# 03.net
KiCad netlist of a schematic drawn in Altium Designer
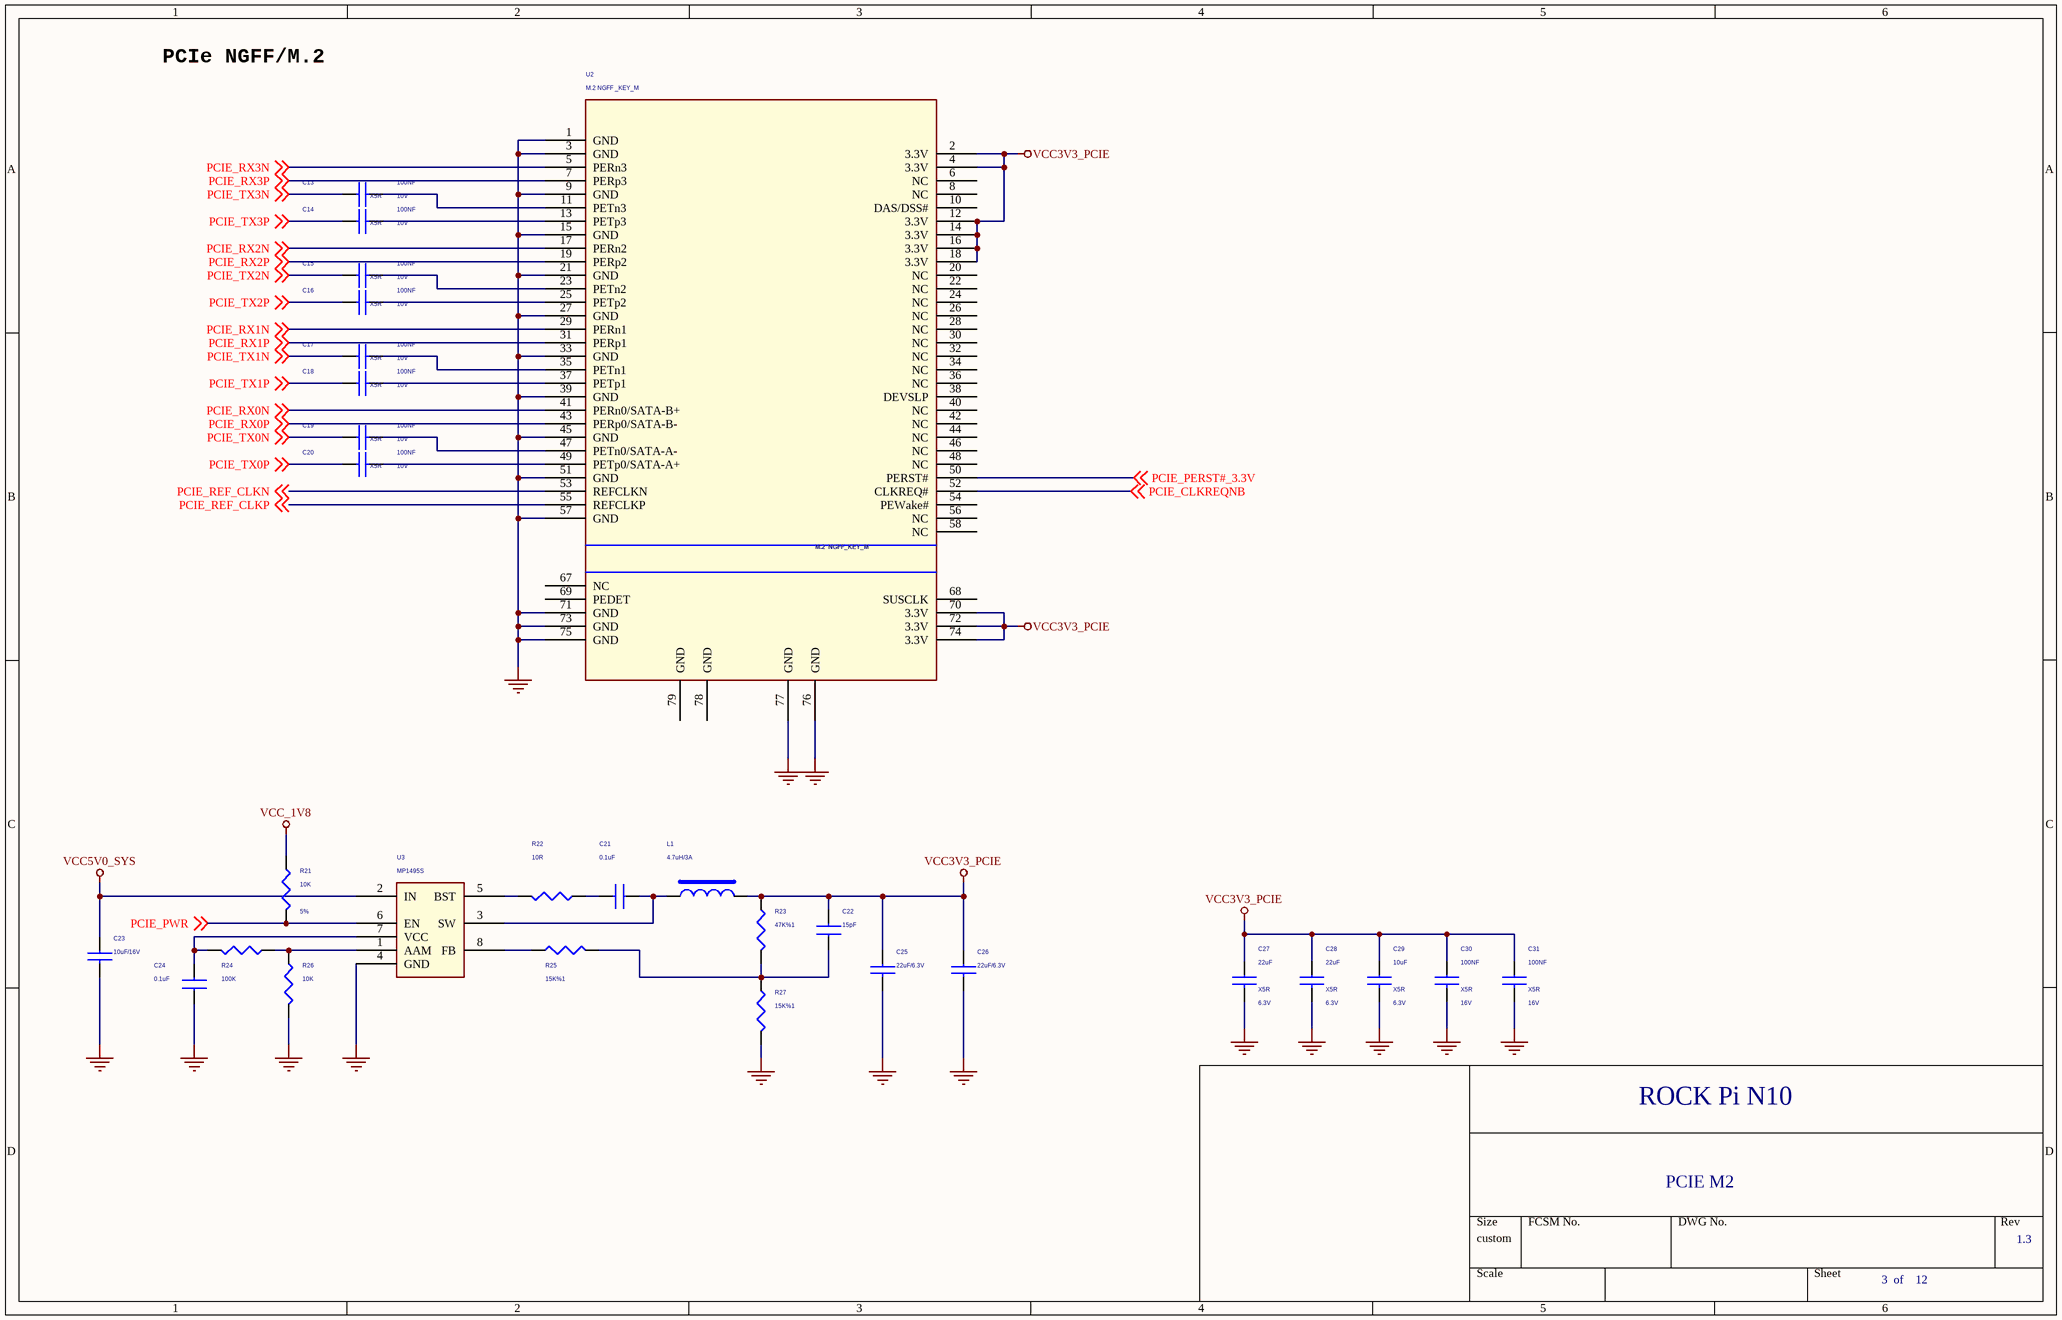
[diagram p0: 03.SchDoc]

(export (version "E")
  (design (tool "Eeschema 10.0.6"))
  (components
    (comp (ref "C13")
      (value "100NF")
      (footprint "C0201")
      (description "cap,100.00nF,+/-10%,10V,X5R,C0201")
      (fields
        (field (name "DIELECTRIC") "X5R")
        (field (name "VOLTAGE") "10V")
        (field (name "MANUFACTURER") "TDK")
        (field (name "TOLERANCE") "10%")
        (field (name "CREATED BY") "JJJ")
      )
      (libsource (lib "*") (part "CAP NP_2"))
    )
    (comp (ref "C14")
      (value "100NF")
      (footprint "C0201")
      (description "cap,100.00nF,+/-10%,10V,X5R,C0201")
      (fields
        (field (name "DIELECTRIC") "X5R")
        (field (name "VOLTAGE") "10V")
        (field (name "MANUFACTURER") "TDK")
        (field (name "TOLERANCE") "10%")
        (field (name "CREATED BY") "JJJ")
      )
      (libsource (lib "*") (part "CAP NP_2"))
    )
    (comp (ref "C15")
      (value "100NF")
      (footprint "C0201")
      (description "cap,100.00nF,+/-10%,10V,X5R,C0201")
      (fields
        (field (name "DIELECTRIC") "X5R")
        (field (name "VOLTAGE") "10V")
        (field (name "MANUFACTURER") "TDK")
        (field (name "TOLERANCE") "10%")
        (field (name "CREATED BY") "JJJ")
      )
      (libsource (lib "*") (part "CAP NP_2"))
    )
    (comp (ref "C16")
      (value "100NF")
      (footprint "C0201")
      (description "cap,100.00nF,+/-10%,10V,X5R,C0201")
      (fields
        (field (name "DIELECTRIC") "X5R")
        (field (name "VOLTAGE") "10V")
        (field (name "MANUFACTURER") "TDK")
        (field (name "TOLERANCE") "10%")
        (field (name "CREATED BY") "JJJ")
      )
      (libsource (lib "*") (part "CAP NP_2"))
    )
    (comp (ref "C17")
      (value "100NF")
      (footprint "C0201")
      (description "cap,100.00nF,+/-10%,10V,X5R,C0201")
      (fields
        (field (name "DIELECTRIC") "X5R")
        (field (name "VOLTAGE") "10V")
        (field (name "MANUFACTURER") "TDK")
        (field (name "TOLERANCE") "10%")
        (field (name "CREATED BY") "JJJ")
      )
      (libsource (lib "*") (part "CAP NP_2"))
    )
    (comp (ref "C18")
      (value "100NF")
      (footprint "C0201")
      (description "cap,100.00nF,+/-10%,10V,X5R,C0201")
      (fields
        (field (name "DIELECTRIC") "X5R")
        (field (name "VOLTAGE") "10V")
        (field (name "MANUFACTURER") "TDK")
        (field (name "TOLERANCE") "10%")
        (field (name "CREATED BY") "JJJ")
      )
      (libsource (lib "*") (part "CAP NP_2"))
    )
    (comp (ref "C19")
      (value "100NF")
      (footprint "C0201")
      (description "cap,100.00nF,+/-10%,10V,X5R,C0201")
      (fields
        (field (name "DIELECTRIC") "X5R")
        (field (name "VOLTAGE") "10V")
        (field (name "TOLERANCE") "10%")
        (field (name "MANUFACTURER") "TDK")
        (field (name "CREATED BY") "JJJ")
      )
      (libsource (lib "*") (part "CAP NP_2"))
    )
    (comp (ref "C20")
      (value "100NF")
      (footprint "C0201")
      (description "cap,100.00nF,+/-10%,10V,X5R,C0201")
      (fields
        (field (name "DIELECTRIC") "X5R")
        (field (name "VOLTAGE") "10V")
        (field (name "TOLERANCE") "10%")
        (field (name "MANUFACTURER") "TDK")
        (field (name "CREATED BY") "JJJ")
      )
      (libsource (lib "*") (part "CAP NP_2"))
    )
    (comp (ref "C21")
      (value "0.1uF")
      (footprint "C0603")
      (description "RoHS CHIP CAP 1uF +10/-10% 16V X5R")
      (libsource (lib "*") (part "CAP NP_Dup3"))
    )
    (comp (ref "C22")
      (value "15pF")
      (footprint "C0603")
      (description "RoHS CHIP CAP 1uF +10/-10% 16V X5R")
      (libsource (lib "*") (part "CAP NP_Dup3"))
    )
    (comp (ref "C23") (value "10uF/16V") (footprint "C0805") (libsource (lib "*") (part "CAP NP_2_Dup1")))
    (comp (ref "C24")
      (value "0.1uF")
      (footprint "C0603")
      (description "RoHS CHIP CAP 1uF +10/-10% 16V X5R")
      (libsource (lib "*") (part "CAP NP_Dup3"))
    )
    (comp (ref "C25") (value "22uF/6.3V") (footprint "C0805") (libsource (lib "*") (part "CAP NP_2_Dup1")))
    (comp (ref "C26") (value "22uF/6.3V") (footprint "C0805") (libsource (lib "*") (part "CAP NP_2_Dup1")))
    (comp (ref "C27")
      (value "22uF")
      (footprint "C0805")
      (description "cap,22.00uF,+/-20%,6.3V,X5R,C0603")
      (fields
        (field (name "DIELECTRIC") "X5R")
        (field (name "VOLTAGE") "6.3V")
        (field (name "MANUFACTURER") "TDK")
        (field (name "TOLERANCE") "20%")
        (field (name "CREATED BY") "JJJ")
      )
      (libsource (lib "*") (part "CAP NP_2"))
    )
    (comp (ref "C28")
      (value "22uF")
      (footprint "C0805")
      (description "cap,22.00uF,+/-20%,6.3V,X5R,C0603")
      (fields
        (field (name "DIELECTRIC") "X5R")
        (field (name "VOLTAGE") "6.3V")
        (field (name "MANUFACTURER") "TDK")
        (field (name "TOLERANCE") "20%")
        (field (name "CREATED BY") "JJJ")
      )
      (libsource (lib "*") (part "CAP NP_2"))
    )
    (comp (ref "C29")
      (value "10uF")
      (footprint "C0603")
      (description "cap,10.00uF,+/-10%,6.3V,X5R,C0603")
      (fields
        (field (name "DIELECTRIC") "X5R")
        (field (name "VOLTAGE") "6.3V")
        (field (name "MANUFACTURER") "TDK")
        (field (name "TOLERANCE") "10%")
        (field (name "CREATED BY") "JJJ")
      )
      (libsource (lib "*") (part "CAP NP_2"))
    )
    (comp (ref "C30")
      (value "100NF")
      (footprint "C0402")
      (description "cap,100.00nF,+/-10%,16V,X5R,C0402")
      (fields
        (field (name "DIELECTRIC") "X5R")
        (field (name "VOLTAGE") "16V")
        (field (name "TOLERANCE") "10%")
        (field (name "MANUFACTURER") "TDK")
        (field (name "CREATED BY") "JJJ")
      )
      (libsource (lib "*") (part "CAP NP_2"))
    )
    (comp (ref "C31")
      (value "100NF")
      (footprint "C0402")
      (description "cap,100.00nF,+/-10%,16V,X5R,C0402")
      (fields
        (field (name "DIELECTRIC") "X5R")
        (field (name "VOLTAGE") "16V")
        (field (name "MANUFACTURER") "TDK")
        (field (name "TOLERANCE") "10%")
        (field (name "CREATED BY") "JJJ")
      )
      (libsource (lib "*") (part "CAP NP_2"))
    )
    (comp (ref "L1")
      (value "4.7uH/3A")
      (footprint "IND-6X6")
      (libsource (lib "*") (part "INDUCTORS OF FERRITE_Dup1"))
    )
    (comp (ref "R21")
      (value "10K")
      (footprint "R0402")
      (description "通用厚膜电阻,10K,+/-5%,R0402,1/16W.")
      (fields
        (field (name "TOLERANCE") "5%")
        (field (name "MANUFACTURER") "YAGEO")
        (field (name "CREATED BY") "YTL")
      )
      (libsource (lib "*") (part "RESISTOR_3"))
    )
    (comp (ref "R22")
      (value "10R")
      (footprint "R0402")
      (description "RES,thick film,47KOhm,+/-5%,1/16W,SMD0402")
      (libsource (lib "*") (part "RESISTOR_0"))
    )
    (comp (ref "R23")
      (value "47K%1")
      (footprint "R0402")
      (description "RES,thick film,47KOhm,+/-5%,1/16W,SMD0402")
      (libsource (lib "*") (part "RESISTOR_0"))
    )
    (comp (ref "R24")
      (value "100K")
      (footprint "R0402")
      (description "RES,thick film,47KOhm,+/-5%,1/16W,SMD0402")
      (libsource (lib "*") (part "RESISTOR_0"))
    )
    (comp (ref "R25")
      (value "15K%1")
      (footprint "R0402")
      (description "RES,thick film,47KOhm,+/-5%,1/16W,SMD0402")
      (libsource (lib "*") (part "RESISTOR_0"))
    )
    (comp (ref "R26")
      (value "10K")
      (footprint "R0402")
      (description "RES,thick film,47KOhm,+/-5%,1/16W,SMD0402")
      (libsource (lib "*") (part "RESISTOR_0"))
    )
    (comp (ref "R27")
      (value "15K%1")
      (footprint "R0402")
      (description "RES,thick film,47KOhm,+/-5%,1/16W,SMD0402")
      (libsource (lib "*") (part "RESISTOR_0"))
    )
    (comp (ref "U2")
      (value "M.2 NGFF _KEY_M")
      (footprint "M2_NGFF_KEY_M")
      (libsource (lib "*") (part "M_5.2 NGFF EKEY SOCKET"))
    )
    (comp (ref "U3") (value "MP1495S") (footprint "TSOT_23_8") (libsource (lib "*") (part "BUCK-MP1495")))
  )
  (nets
    (net (code "1") (name "GND") (class "Default")
      (node (ref "C23") (pin "2") (pinfunction "2_2") (pintype "passive"))
      (node (ref "C24") (pin "1") (pinfunction "1_1") (pintype "passive"))
      (node (ref "C25") (pin "2") (pinfunction "2_2") (pintype "passive"))
      (node (ref "C26") (pin "2") (pinfunction "2_2") (pintype "passive"))
      (node (ref "C27") (pin "2") (pinfunction "2_2") (pintype "passive"))
      (node (ref "C28") (pin "2") (pinfunction "2_2") (pintype "passive"))
      (node (ref "C29") (pin "2") (pinfunction "2_2") (pintype "passive"))
      (node (ref "C30") (pin "2") (pinfunction "2_2") (pintype "passive"))
      (node (ref "C31") (pin "2") (pinfunction "2_2") (pintype "passive"))
      (node (ref "R26") (pin "2") (pinfunction "2_2") (pintype "passive"))
      (node (ref "R27") (pin "2") (pinfunction "2_2") (pintype "passive"))
      (node (ref "U2") (pin "1") (pinfunction "GND_1") (pintype "passive"))
      (node (ref "U2") (pin "15") (pinfunction "GND_15") (pintype "passive"))
      (node (ref "U2") (pin "21") (pinfunction "GND_21") (pintype "passive"))
      (node (ref "U2") (pin "27") (pinfunction "GND_27") (pintype "passive"))
      (node (ref "U2") (pin "3") (pinfunction "GND_3") (pintype "passive"))
      (node (ref "U2") (pin "33") (pinfunction "GND_33") (pintype "passive"))
      (node (ref "U2") (pin "39") (pinfunction "GND_39") (pintype "passive"))
      (node (ref "U2") (pin "45") (pinfunction "GND_45") (pintype "passive"))
      (node (ref "U2") (pin "51") (pinfunction "GND_51") (pintype "passive"))
      (node (ref "U2") (pin "57") (pinfunction "GND_57") (pintype "passive"))
      (node (ref "U2") (pin "71") (pinfunction "GND_71") (pintype "passive"))
      (node (ref "U2") (pin "73") (pinfunction "GND_73") (pintype "passive"))
      (node (ref "U2") (pin "75") (pinfunction "GND_75") (pintype "passive"))
      (node (ref "U2") (pin "76") (pinfunction "GND_76") (pintype "passive"))
      (node (ref "U2") (pin "77") (pinfunction "GND_77") (pintype "passive"))
      (node (ref "U2") (pin "9") (pinfunction "GND_9") (pintype "passive"))
      (node (ref "U3") (pin "4") (pinfunction "GND_4") (pintype "passive"))
    )
    (net (code "2") (name "Net-(C21-Pad2)") (class "Default")
      (node (ref "C21") (pin "2") (pinfunction "2_2") (pintype "passive"))
      (node (ref "R22") (pin "1") (pinfunction "1_1") (pintype "passive"))
    )
    (net (code "3") (name "Net-(C22-Pad1)") (class "Default")
      (node (ref "C22") (pin "1") (pinfunction "1_1") (pintype "passive"))
      (node (ref "R23") (pin "2") (pinfunction "2_2") (pintype "passive"))
      (node (ref "R25") (pin "2") (pinfunction "2_2") (pintype "passive"))
      (node (ref "R27") (pin "1") (pinfunction "1_1") (pintype "passive"))
    )
    (net (code "4") (name "Net-(U2-PETn0{slash}SATA-A-)") (class "Default")
      (node (ref "C19") (pin "2") (pinfunction "2_2") (pintype "passive"))
      (node (ref "U2") (pin "47") (pinfunction "PETn0/SATA-A-_47") (pintype "passive"))
    )
    (net (code "5") (name "Net-(U2-PETn1)") (class "Default")
      (node (ref "C17") (pin "2") (pinfunction "2_2") (pintype "passive"))
      (node (ref "U2") (pin "35") (pinfunction "PETn1_35") (pintype "passive"))
    )
    (net (code "6") (name "Net-(U2-PETn2)") (class "Default")
      (node (ref "C15") (pin "2") (pinfunction "2_2") (pintype "passive"))
      (node (ref "U2") (pin "23") (pinfunction "PETn2_23") (pintype "passive"))
    )
    (net (code "7") (name "Net-(U2-PETn3)") (class "Default")
      (node (ref "C13") (pin "2") (pinfunction "2_2") (pintype "passive"))
      (node (ref "U2") (pin "11") (pinfunction "PETn3_11") (pintype "passive"))
    )
    (net (code "8") (name "Net-(U2-PETp0{slash}SATA-A+)") (class "Default")
      (node (ref "C20") (pin "2") (pinfunction "2_2") (pintype "passive"))
      (node (ref "U2") (pin "49") (pinfunction "PETp0/SATA-A+_49") (pintype "passive"))
    )
    (net (code "9") (name "Net-(U2-PETp1)") (class "Default")
      (node (ref "C18") (pin "2") (pinfunction "2_2") (pintype "passive"))
      (node (ref "U2") (pin "37") (pinfunction "PETp1_37") (pintype "passive"))
    )
    (net (code "10") (name "Net-(U2-PETp2)") (class "Default")
      (node (ref "C16") (pin "2") (pinfunction "2_2") (pintype "passive"))
      (node (ref "U2") (pin "25") (pinfunction "PETp2_25") (pintype "passive"))
    )
    (net (code "11") (name "Net-(U2-PETp3)") (class "Default")
      (node (ref "C14") (pin "2") (pinfunction "2_2") (pintype "passive"))
      (node (ref "U2") (pin "13") (pinfunction "PETp3_13") (pintype "passive"))
    )
    (net (code "12") (name "Net-(U3-AAM)") (class "Default")
      (node (ref "R24") (pin "1") (pinfunction "1_1") (pintype "passive"))
      (node (ref "R26") (pin "1") (pinfunction "1_1") (pintype "passive"))
      (node (ref "U3") (pin "1") (pinfunction "AAM_1") (pintype "passive"))
    )
    (net (code "13") (name "Net-(U3-BST)") (class "Default")
      (node (ref "R22") (pin "2") (pinfunction "2_2") (pintype "passive"))
      (node (ref "U3") (pin "5") (pinfunction "BST_5") (pintype "passive"))
    )
    (net (code "14") (name "Net-(U3-FB)") (class "Default")
      (node (ref "R25") (pin "1") (pinfunction "1_1") (pintype "passive"))
      (node (ref "U3") (pin "8") (pinfunction "FB_8") (pintype "passive"))
    )
    (net (code "15") (name "Net-(U3-SW)") (class "Default")
      (node (ref "C21") (pin "1") (pinfunction "1_1") (pintype "passive"))
      (node (ref "L1") (pin "1") (pinfunction "1_1") (pintype "passive"))
      (node (ref "U3") (pin "3") (pinfunction "SW_3") (pintype "passive"))
    )
    (net (code "16") (name "Net-(U3-VCC)") (class "Default")
      (node (ref "C24") (pin "2") (pinfunction "2_2") (pintype "passive"))
      (node (ref "R24") (pin "2") (pinfunction "2_2") (pintype "passive"))
      (node (ref "U3") (pin "7") (pinfunction "VCC_7") (pintype "passive"))
    )
    (net (code "17") (name "PCIE_CLKREQNB") (class "Default")
      (node (ref "U2") (pin "52") (pinfunction "CLKREQ#_52") (pintype "passive"))
    )
    (net (code "18") (name "PCIE_PERST#_3.3V") (class "Default")
      (node (ref "U2") (pin "50") (pinfunction "PERST#_50") (pintype "passive"))
    )
    (net (code "19") (name "PCIE_PWR") (class "Default")
      (node (ref "R21") (pin "2") (pinfunction "2_2") (pintype "passive"))
      (node (ref "U3") (pin "6") (pinfunction "EN_6") (pintype "passive"))
    )
    (net (code "20") (name "PCIE_REF_CLKN") (class "Default")
      (node (ref "U2") (pin "53") (pinfunction "REFCLKN_53") (pintype "passive"))
    )
    (net (code "21") (name "PCIE_REF_CLKP") (class "Default")
      (node (ref "U2") (pin "55") (pinfunction "REFCLKP_55") (pintype "passive"))
    )
    (net (code "22") (name "PCIE_RX0N") (class "Default")
      (node (ref "U2") (pin "41") (pinfunction "PERn0/SATA-B+_41") (pintype "passive"))
    )
    (net (code "23") (name "PCIE_RX0P") (class "Default")
      (node (ref "U2") (pin "43") (pinfunction "PERp0/SATA-B-_43") (pintype "passive"))
    )
    (net (code "24") (name "PCIE_RX1N") (class "Default")
      (node (ref "U2") (pin "29") (pinfunction "PERn1_29") (pintype "passive"))
    )
    (net (code "25") (name "PCIE_RX1P") (class "Default")
      (node (ref "U2") (pin "31") (pinfunction "PERp1_31") (pintype "passive"))
    )
    (net (code "26") (name "PCIE_RX2N") (class "Default")
      (node (ref "U2") (pin "17") (pinfunction "PERn2_17") (pintype "passive"))
    )
    (net (code "27") (name "PCIE_RX2P") (class "Default")
      (node (ref "U2") (pin "19") (pinfunction "PERp2_19") (pintype "passive"))
    )
    (net (code "28") (name "PCIE_RX3N") (class "Default")
      (node (ref "U2") (pin "5") (pinfunction "PERn3_5") (pintype "passive"))
    )
    (net (code "29") (name "PCIE_RX3P") (class "Default")
      (node (ref "U2") (pin "7") (pinfunction "PERp3_7") (pintype "passive"))
    )
    (net (code "30") (name "PCIE_TX0N") (class "Default")
      (node (ref "C19") (pin "1") (pinfunction "1_1") (pintype "passive"))
    )
    (net (code "31") (name "PCIE_TX0P") (class "Default")
      (node (ref "C20") (pin "1") (pinfunction "1_1") (pintype "passive"))
    )
    (net (code "32") (name "PCIE_TX1N") (class "Default")
      (node (ref "C17") (pin "1") (pinfunction "1_1") (pintype "passive"))
    )
    (net (code "33") (name "PCIE_TX1P") (class "Default")
      (node (ref "C18") (pin "1") (pinfunction "1_1") (pintype "passive"))
    )
    (net (code "34") (name "PCIE_TX2N") (class "Default")
      (node (ref "C15") (pin "1") (pinfunction "1_1") (pintype "passive"))
    )
    (net (code "35") (name "PCIE_TX2P") (class "Default")
      (node (ref "C16") (pin "1") (pinfunction "1_1") (pintype "passive"))
    )
    (net (code "36") (name "PCIE_TX3N") (class "Default")
      (node (ref "C13") (pin "1") (pinfunction "1_1") (pintype "passive"))
    )
    (net (code "37") (name "PCIE_TX3P") (class "Default")
      (node (ref "C14") (pin "1") (pinfunction "1_1") (pintype "passive"))
    )
    (net (code "38") (name "VCC3V3_PCIE") (class "Default")
      (node (ref "C22") (pin "2") (pinfunction "2_2") (pintype "passive"))
      (node (ref "C25") (pin "1") (pinfunction "1_1") (pintype "passive"))
      (node (ref "C26") (pin "1") (pinfunction "1_1") (pintype "passive"))
      (node (ref "C27") (pin "1") (pinfunction "1_1") (pintype "passive"))
      (node (ref "C28") (pin "1") (pinfunction "1_1") (pintype "passive"))
      (node (ref "C29") (pin "1") (pinfunction "1_1") (pintype "passive"))
      (node (ref "C30") (pin "1") (pinfunction "1_1") (pintype "passive"))
      (node (ref "C31") (pin "1") (pinfunction "1_1") (pintype "passive"))
      (node (ref "L1") (pin "2") (pinfunction "2_2") (pintype "passive"))
      (node (ref "R23") (pin "1") (pinfunction "1_1") (pintype "passive"))
      (node (ref "U2") (pin "12") (pinfunction "3.3V_12") (pintype "passive"))
      (node (ref "U2") (pin "14") (pinfunction "3.3V_14") (pintype "passive"))
      (node (ref "U2") (pin "16") (pinfunction "3.3V_16") (pintype "passive"))
      (node (ref "U2") (pin "18") (pinfunction "3.3V_18") (pintype "passive"))
      (node (ref "U2") (pin "2") (pinfunction "3.3V_2") (pintype "passive"))
      (node (ref "U2") (pin "4") (pinfunction "3.3V_4") (pintype "passive"))
      (node (ref "U2") (pin "70") (pinfunction "3.3V_70") (pintype "passive"))
      (node (ref "U2") (pin "72") (pinfunction "3.3V_72") (pintype "passive"))
      (node (ref "U2") (pin "74") (pinfunction "3.3V_74") (pintype "passive"))
    )
    (net (code "39") (name "VCC5V0_SYS") (class "Default")
      (node (ref "C23") (pin "1") (pinfunction "1_1") (pintype "passive"))
      (node (ref "U3") (pin "2") (pinfunction "IN_2") (pintype "passive"))
    )
    (net (code "40") (name "VCC_1V8") (class "Default")
      (node (ref "R21") (pin "1") (pinfunction "1_1") (pintype "passive"))
    )
    (net (code "41") (name "unconnected-(U2-DAS{slash}DSS#-Pad10)") (class "Default")
      (node (ref "U2") (pin "10") (pinfunction "DAS/DSS#_10") (pintype "passive"))
    )
    (net (code "42") (name "unconnected-(U2-DEVSLP-Pad38)") (class "Default")
      (node (ref "U2") (pin "38") (pinfunction "DEVSLP_38") (pintype "passive"))
    )
    (net (code "43") (name "unconnected-(U2-GND-Pad78)") (class "Default")
      (node (ref "U2") (pin "78") (pinfunction "GND_78") (pintype "passive"))
    )
    (net (code "44") (name "unconnected-(U2-GND-Pad79)") (class "Default")
      (node (ref "U2") (pin "79") (pinfunction "GND_79") (pintype "passive"))
    )
    (net (code "45") (name "unconnected-(U2-NC-Pad6)") (class "Default")
      (node (ref "U2") (pin "6") (pinfunction "NC_6") (pintype "passive"))
    )
    (net (code "46") (name "unconnected-(U2-NC-Pad8)") (class "Default")
      (node (ref "U2") (pin "8") (pinfunction "NC_8") (pintype "passive"))
    )
    (net (code "47") (name "unconnected-(U2-NC-Pad20)") (class "Default")
      (node (ref "U2") (pin "20") (pinfunction "NC_20") (pintype "passive"))
    )
    (net (code "48") (name "unconnected-(U2-NC-Pad22)") (class "Default")
      (node (ref "U2") (pin "22") (pinfunction "NC_22") (pintype "passive"))
    )
    (net (code "49") (name "unconnected-(U2-NC-Pad24)") (class "Default")
      (node (ref "U2") (pin "24") (pinfunction "NC_24") (pintype "passive"))
    )
    (net (code "50") (name "unconnected-(U2-NC-Pad26)") (class "Default")
      (node (ref "U2") (pin "26") (pinfunction "NC_26") (pintype "passive"))
    )
    (net (code "51") (name "unconnected-(U2-NC-Pad28)") (class "Default")
      (node (ref "U2") (pin "28") (pinfunction "NC_28") (pintype "passive"))
    )
    (net (code "52") (name "unconnected-(U2-NC-Pad30)") (class "Default")
      (node (ref "U2") (pin "30") (pinfunction "NC_30") (pintype "passive"))
    )
    (net (code "53") (name "unconnected-(U2-NC-Pad32)") (class "Default")
      (node (ref "U2") (pin "32") (pinfunction "NC_32") (pintype "passive"))
    )
    (net (code "54") (name "unconnected-(U2-NC-Pad34)") (class "Default")
      (node (ref "U2") (pin "34") (pinfunction "NC_34") (pintype "passive"))
    )
    (net (code "55") (name "unconnected-(U2-NC-Pad36)") (class "Default")
      (node (ref "U2") (pin "36") (pinfunction "NC_36") (pintype "passive"))
    )
    (net (code "56") (name "unconnected-(U2-NC-Pad40)") (class "Default")
      (node (ref "U2") (pin "40") (pinfunction "NC_40") (pintype "passive"))
    )
    (net (code "57") (name "unconnected-(U2-NC-Pad42)") (class "Default")
      (node (ref "U2") (pin "42") (pinfunction "NC_42") (pintype "passive"))
    )
    (net (code "58") (name "unconnected-(U2-NC-Pad44)") (class "Default")
      (node (ref "U2") (pin "44") (pinfunction "NC_44") (pintype "passive"))
    )
    (net (code "59") (name "unconnected-(U2-NC-Pad46)") (class "Default")
      (node (ref "U2") (pin "46") (pinfunction "NC_46") (pintype "passive"))
    )
    (net (code "60") (name "unconnected-(U2-NC-Pad48)") (class "Default")
      (node (ref "U2") (pin "48") (pinfunction "NC_48") (pintype "passive"))
    )
    (net (code "61") (name "unconnected-(U2-NC-Pad56)") (class "Default")
      (node (ref "U2") (pin "56") (pinfunction "NC_56") (pintype "passive"))
    )
    (net (code "62") (name "unconnected-(U2-NC-Pad58)") (class "Default")
      (node (ref "U2") (pin "58") (pinfunction "NC_58") (pintype "passive"))
    )
    (net (code "63") (name "unconnected-(U2-NC-Pad67)") (class "Default")
      (node (ref "U2") (pin "67") (pinfunction "NC_67") (pintype "passive"))
    )
    (net (code "64") (name "unconnected-(U2-PEDET-Pad69)") (class "Default")
      (node (ref "U2") (pin "69") (pinfunction "PEDET_69") (pintype "passive"))
    )
    (net (code "65") (name "unconnected-(U2-PEWake#-Pad54)") (class "Default")
      (node (ref "U2") (pin "54") (pinfunction "PEWake#_54") (pintype "passive"))
    )
    (net (code "66") (name "unconnected-(U2-SUSCLK-Pad68)") (class "Default")
      (node (ref "U2") (pin "68") (pinfunction "SUSCLK_68") (pintype "passive"))
    )
  )
)
